# NCS_Wireless_Control_Card_Power_dis_conn.net
KiCad netlist of a schematic drawn in Altium Designer
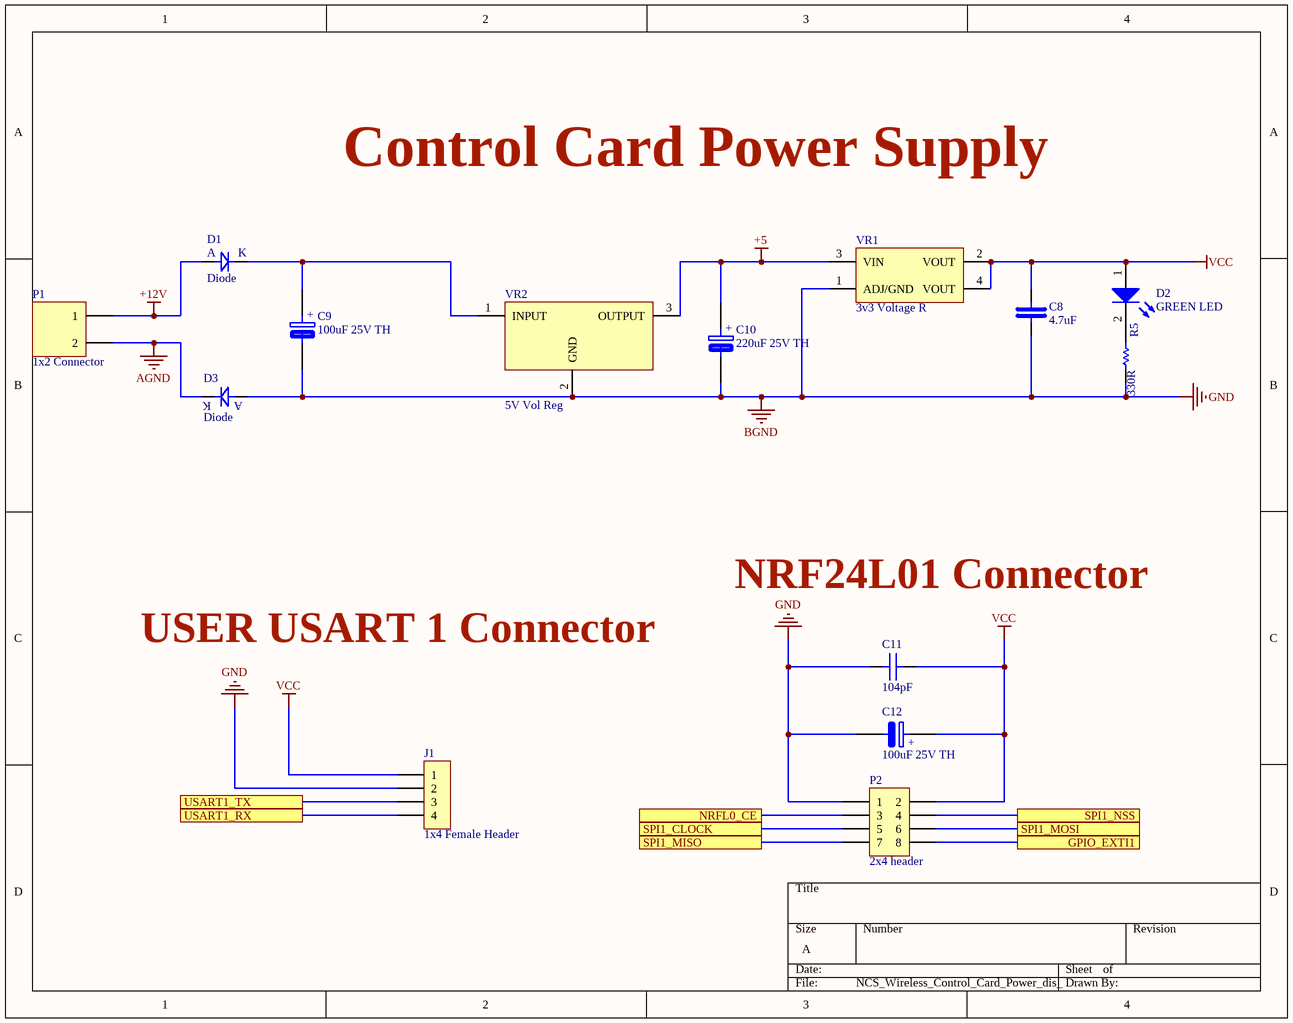
[diagram p0: NCS_Wireless_Control_Card_Power_dis_conn.SchDoc]

(export (version "E")
  (design (tool "Eeschema 10.0.6"))
  (components
    (comp (ref "C8")
      (value "4.7uF")
      (footprint "C0805C209D3HACTU_2pF")
      (description "Multilayer Ceramic Capacitor, 4.7 uF, 25 V, ï¿½ 10%, X5R, 0805 [2012 Metric]")
      (fields
        (field (name "MANUFACTURER") "KEMET")
        (field (name "MANUFACTURER PART NUMBER") "C0805C475K3PACTU")
      )
      (libsource (lib "schlib") (part "C0805C475K3PACTU"))
    )
    (comp (ref "C9")
      (value "100uF 25V TH")
      (footprint "100uF 25V TH")
      (description "WCAP-ATG8 Aluminum Electrolytic Capacitors")
      (fields
        (field (name "MANUFACTURER") "Wurth Electronics")
        (field (name "MANUFACTURER PART NUMBER") "860010473007")
      )
      (libsource (lib "schlib") (part "860010473007"))
    )
    (comp (ref "C10")
      (value "220uF 25V TH")
      (footprint "100uF 25V TH")
      (description "WCAP-ATG8 Aluminum Electrolytic Capacitors")
      (fields
        (field (name "MANUFACTURER") "Wurth Electronics")
        (field (name "MANUFACTURER PART NUMBER") "860010473007")
      )
      (libsource (lib "schlib") (part "860010473007"))
    )
    (comp (ref "C11")
      (value "104pF")
      (footprint "C0805C471K3RACTU_470pF")
      (description "Capacitor, Ceramic, 470pF, 25VDC, 10-% Tol, 10+% Tol, X7R-TC Code, -15, 15%-TC RoHS Compliant: Yes")
      (fields
        (field (name "MANUFACTURER") "KEMET")
        (field (name "MANUFACTURER PART NUMBER") "C0805C471K3RACTU")
      )
      (libsource (lib "schlib") (part "C0805C471K3RACTU"))
    )
    (comp (ref "C12")
      (value "100uF 25V TH")
      (footprint "100uF 25V TH")
      (description "WCAP-ATG8 Aluminum Electrolytic Capacitors")
      (fields
        (field (name "MANUFACTURER") "Wurth Electronics")
        (field (name "MANUFACTURER PART NUMBER") "860010473007")
      )
      (libsource (lib "schlib") (part "860010473007"))
    )
    (comp (ref "D1")
      (value "Diode")
      (footprint "CRS06(TE85L,Q,M)_DIODE")
      (description "Diode Schottky 20V 1A 2-Pin S-FLAT T/R / DIODE SCHOTTKY 20V 1A SFLAT")
      (fields
        (field (name "MANUFACTURER") "Toshiba")
        (field (name "MANUFACTURER PART NUMBER") "CRS06(TE85L,Q,M)")
      )
      (libsource (lib "schlib") (part "CRS06(TE85L,Q,M)"))
    )
    (comp (ref "D2")
      (value "GREEN LED")
      (footprint "LTST-C171GKT_GREEN")
      (description "LED Low-Power Uni-Color Green 565nm 2.1V 2-Pin Chip LED T/R")
      (fields
        (field (name "MANUFACTURER") "Vishay Lite-On")
        (field (name "MANUFACTURER PART NUMBER") "LTST-C171GKT")
      )
      (libsource (lib "schlib") (part "LTST-C171GKT"))
    )
    (comp (ref "D3")
      (value "Diode")
      (footprint "CRS06(TE85L,Q,M)_DIODE")
      (description "Diode Schottky 20V 1A 2-Pin S-FLAT T/R / DIODE SCHOTTKY 20V 1A SFLAT")
      (fields
        (field (name "MANUFACTURER") "Toshiba")
        (field (name "MANUFACTURER PART NUMBER") "CRS06(TE85L,Q,M)")
      )
      (libsource (lib "schlib") (part "CRS06(TE85L,Q,M)"))
    )
    (comp (ref "J1")
      (value "1x4 Female Header")
      (footprint "1x4 Female Header")
      (description "Female, 4 C, Straight, .100\"CC; 3.20mm Tail, No Mounting; PBT, Phos. Bronze, 105 C")
      (fields
        (field (name "MANUFACTURER") "Sullins")
        (field (name "MANUFACTURER PART NUMBER") "PPPC041LFBN-RC")
      )
      (libsource (lib "schlib") (part "PPPC041LFBN-RC"))
    )
    (comp (ref "P1")
      (value "1x2 Connector")
      (footprint "1x2 Connector")
      (description "2~24 Poles, Screw Type, Horizontal, 5.08 Pitch, 26~14 (AWG), Terminal Block Connector")
      (fields (field (name "MANUFACTURER") "CUI") (field (name "MANUFACTURER PART NUMBER") "TB006-508-02BE"))
      (libsource (lib "schlib") (part "TB006-508-02BE"))
    )
    (comp (ref "P2")
      (value "2x4 header")
      (footprint "2x4 header")
      (description "Header Connector, Pcb Mnt, 8 Contacts, Skt, 0.1 Pitch, Pc Tail Terminal, Locking")
      (fields
        (field (name "MANUFACTURER") "Sullins")
        (field (name "MANUFACTURER PART NUMBER") "PPTC042LFBN-RC")
      )
      (libsource (lib "schlib") (part "PPTC042LFBN-RC"))
    )
    (comp (ref "R5")
      (value "330R")
      (footprint "RC0805FR-7W330RL")
      (description "Res Thick Film 0805 330 Ohm 1% 0.25W(1/4W) ±200ppm/C Pad SMD T/R")
      (fields
        (field (name "MANUFACTURER") "Yageo")
        (field (name "MANUFACTURER PART NUMBER") "RC0805FR-7W330RL")
      )
      (libsource (lib "schlib") (part "RC0805FR-7W330RL"))
    )
    (comp (ref "VR1")
      (value "3v3 Voltage R")
      (footprint "SAMS1117-33-4N")
      (libsource (lib "NCS_Wireless_Bed_Unit") (part "AMS1117-33-3.3V"))
    )
    (comp (ref "VR2")
      (value "5V Vol Reg")
      (footprint "5V Vol Reg DIP")
      (description "Voltage Regulator; linear; fixed; Vout: 5V; Vin: 7-35V; Vd: 2V; 2%; 1A; 0+150 deg.C; THT; TO220")
      (fields
        (field (name "MANUFACTURER") "STMicroelectronics")
        (field (name "MANUFACTURER PART NUMBER") "L7805CV")
      )
      (libsource (lib "schlib") (part "L7805CV"))
    )
  )
  (nets
    (net (code "1") (name "+5") (class "Default")
      (node (ref "C10") (pin "1") (pinfunction "1_1") (pintype "passive"))
      (node (ref "VR1") (pin "3") (pinfunction "VIN_3") (pintype "passive"))
      (node (ref "VR2") (pin "3") (pinfunction "OUTPUT_3") (pintype "passive"))
    )
    (net (code "2") (name "+12V") (class "Default")
      (node (ref "D1") (pin "1") (pinfunction "1_1") (pintype "passive"))
      (node (ref "P1") (pin "1") (pinfunction "1_1") (pintype "passive"))
    )
    (net (code "3") (name "/GPIO_EXTI1") (class "Default")
      (node (ref "P2") (pin "8") (pinfunction "8_8") (pintype "passive"))
    )
    (net (code "4") (name "/NRFL0_CE") (class "Default")
      (node (ref "P2") (pin "3") (pinfunction "3_3") (pintype "passive"))
    )
    (net (code "5") (name "/SPI1_CLOCK") (class "Default")
      (node (ref "P2") (pin "5") (pinfunction "5_5") (pintype "passive"))
    )
    (net (code "6") (name "/SPI1_MISO") (class "Default")
      (node (ref "P2") (pin "7") (pinfunction "7_7") (pintype "passive"))
    )
    (net (code "7") (name "/SPI1_MOSI") (class "Default")
      (node (ref "P2") (pin "6") (pinfunction "6_6") (pintype "passive"))
    )
    (net (code "8") (name "/SPI1_NSS") (class "Default")
      (node (ref "P2") (pin "4") (pinfunction "4_4") (pintype "passive"))
    )
    (net (code "9") (name "/USART1_RX") (class "Default")
      (node (ref "J1") (pin "4") (pinfunction "4_4") (pintype "passive"))
    )
    (net (code "10") (name "/USART1_TX") (class "Default")
      (node (ref "J1") (pin "3") (pinfunction "3_3") (pintype "passive"))
    )
    (net (code "11") (name "AGND") (class "Default")
      (node (ref "D3") (pin "2") (pinfunction "2_2") (pintype "passive"))
      (node (ref "P1") (pin "2") (pinfunction "2_2") (pintype "passive"))
    )
    (net (code "12") (name "BGND") (class "Default")
      (node (ref "C10") (pin "2") (pinfunction "2_2") (pintype "passive"))
      (node (ref "C11") (pin "1") (pinfunction "1_1") (pintype "passive"))
      (node (ref "C12") (pin "2") (pinfunction "2_2") (pintype "passive"))
      (node (ref "C8") (pin "1") (pinfunction "1_1") (pintype "passive"))
      (node (ref "C9") (pin "2") (pinfunction "2_2") (pintype "passive"))
      (node (ref "D3") (pin "1") (pinfunction "1_1") (pintype "passive"))
      (node (ref "J1") (pin "2") (pinfunction "2_2") (pintype "passive"))
      (node (ref "P2") (pin "1") (pinfunction "1_1") (pintype "passive"))
      (node (ref "R5") (pin "1") (pinfunction "1_1") (pintype "passive"))
      (node (ref "VR1") (pin "1") (pinfunction "ADJ/GND_1") (pintype "passive"))
      (node (ref "VR2") (pin "2") (pinfunction "GND_2") (pintype "passive"))
    )
    (net (code "13") (name "Net-(D2-K)") (class "Default")
      (node (ref "D2") (pin "2") (pinfunction "K_2") (pintype "passive"))
      (node (ref "R5") (pin "2") (pinfunction "2_2") (pintype "passive"))
    )
    (net (code "14") (name "Net-(VR2-INPUT)") (class "Default")
      (node (ref "C9") (pin "1") (pinfunction "1_1") (pintype "passive"))
      (node (ref "D1") (pin "2") (pinfunction "2_2") (pintype "passive"))
      (node (ref "VR2") (pin "1") (pinfunction "INPUT_1") (pintype "passive"))
    )
    (net (code "15") (name "VCC") (class "Default")
      (node (ref "C11") (pin "2") (pinfunction "2_2") (pintype "passive"))
      (node (ref "C12") (pin "1") (pinfunction "1_1") (pintype "passive"))
      (node (ref "C8") (pin "2") (pinfunction "2_2") (pintype "passive"))
      (node (ref "D2") (pin "1") (pinfunction "A_1") (pintype "passive"))
      (node (ref "J1") (pin "1") (pinfunction "1_1") (pintype "passive"))
      (node (ref "P2") (pin "2") (pinfunction "2_2") (pintype "passive"))
      (node (ref "VR1") (pin "2") (pinfunction "VOUT_2") (pintype "passive"))
      (node (ref "VR1") (pin "4") (pinfunction "VOUT_4") (pintype "passive"))
    )
  )
)
